# TVR_Rev2_Power.net
KiCad netlist of a schematic drawn in Altium Designer
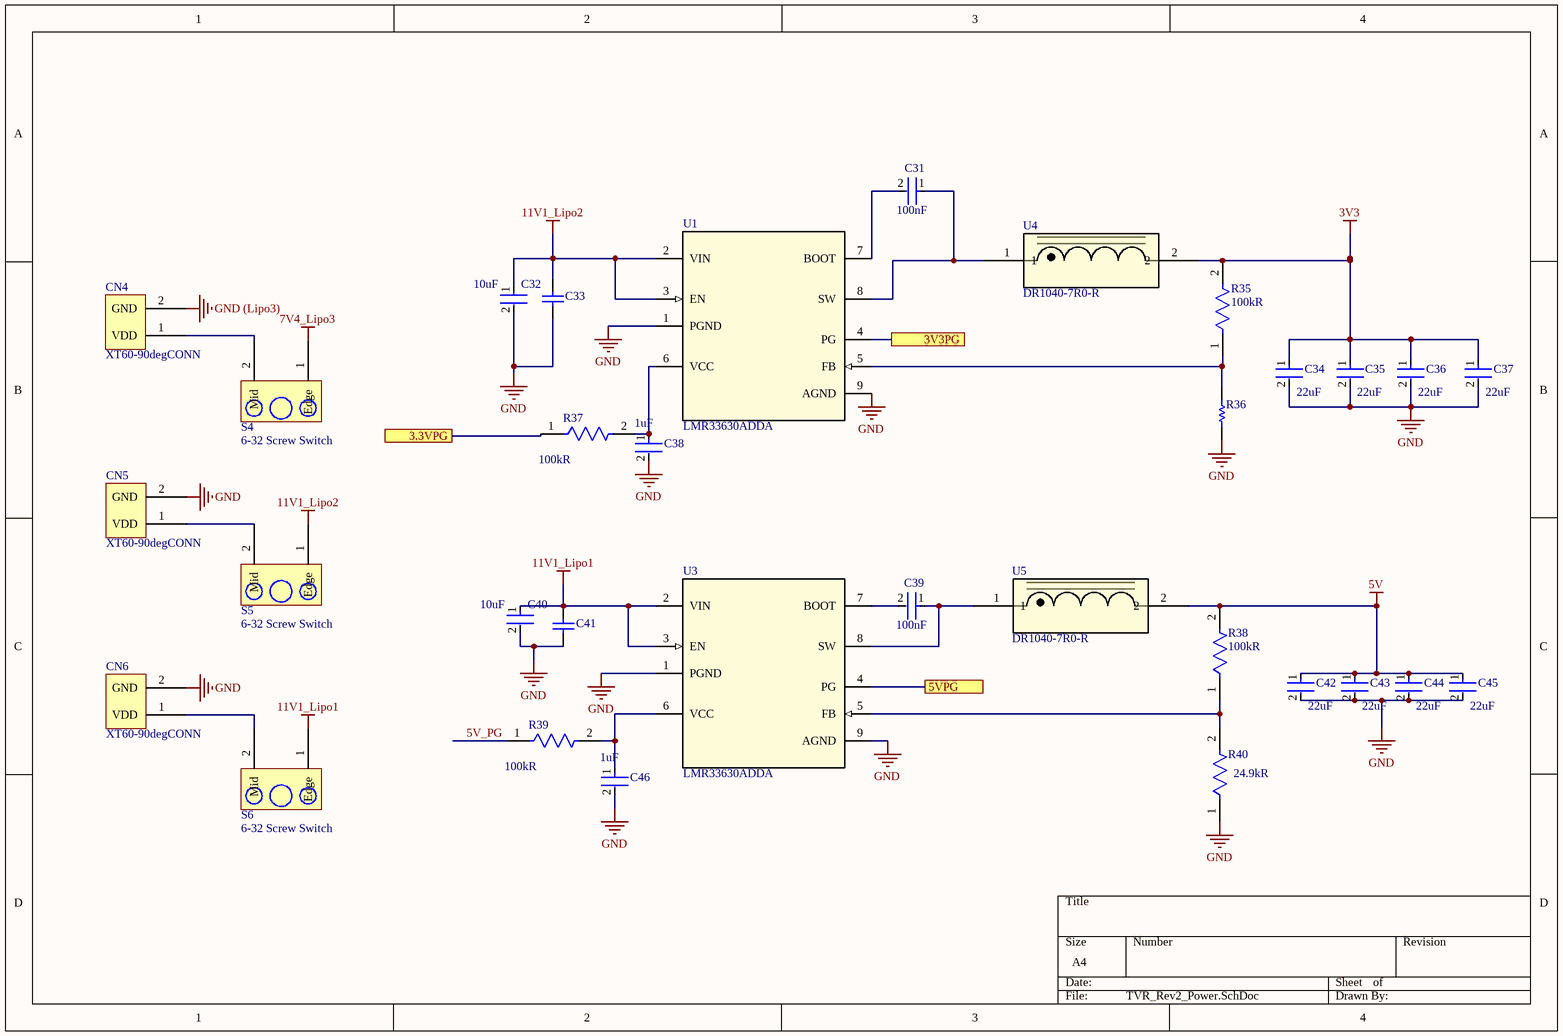
[diagram p0: TVR_Rev2_Power.SchDoc]

(export (version "E")
  (design (tool "Eeschema 10.0.6"))
  (components
    (comp (ref "C31")
      (value "C2012X7T2E104K125AE")
      (footprint "FP-C2012-125-0_45-MFG")
      (description "CAP CER 0.1UF 250V X7T 0805")
      (fields (field (name "CAPACITANCE") "100nF") (field (name "TOLERANCE") "10%"))
      (libsource (lib "Altium Content Vault") (part "b4654b650e69147ec39a6b967a45e02"))
    )
    (comp (ref "C32")
      (value "GRM21BR61E106KA73L")
      (footprint "FP-GRM21B-0_15-IPC_C")
      (description "Chip Multilayer Ceramic Capacitors for General Purpose, 0805, 10uF, X5R, 15%, 10%, 25V")
      (fields
        (field (name "VOLTAGE") "25V")
        (field (name "CAPACITANCE") "10uF")
        (field (name "TOLERANCE") "10%")
      )
      (libsource (lib "Altium Content Vault") (part "b4654b650e69147ec39a6b967a45e02"))
    )
    (comp (ref "C33")
      (value "08051C224KAT2A")
      (footprint "CAPC2013X94X50ML20T25")
      (fields (field (name "MANUFACTURER") "AVX Interconnect / Elco"))
      (libsource (lib "Altium Content Vault") (part "CAP"))
    )
    (comp (ref "C34")
      (value "CL21A226KOQNNNG")
      (footprint "FP-CL21-IPC_A")
      (description "CL21 Series 0805 22uF 16V ±10% Tolerance X5R Multilayer Ceramic Chip Capacitor")
      (fields (field (name "TOLERANCE") "10%") (field (name "CAPACITANCE") "22uF"))
      (libsource (lib "Altium Content Vault") (part "b4654b650e69147ec39a6b967a45e02"))
    )
    (comp (ref "C35")
      (value "CL21A226KOQNNNG")
      (footprint "FP-CL21-IPC_A")
      (description "CL21 Series 0805 22uF 16V ±10% Tolerance X5R Multilayer Ceramic Chip Capacitor")
      (fields (field (name "TOLERANCE") "10%") (field (name "CAPACITANCE") "22uF"))
      (libsource (lib "Altium Content Vault") (part "b4654b650e69147ec39a6b967a45e02"))
    )
    (comp (ref "C36")
      (value "CL21A226KOQNNNG")
      (footprint "FP-CL21-IPC_A")
      (description "CL21 Series 0805 22uF 16V ±10% Tolerance X5R Multilayer Ceramic Chip Capacitor")
      (fields (field (name "TOLERANCE") "10%") (field (name "CAPACITANCE") "22uF"))
      (libsource (lib "Altium Content Vault") (part "b4654b650e69147ec39a6b967a45e02"))
    )
    (comp (ref "C37")
      (value "CL21A226KOQNNNG")
      (footprint "FP-CL21-IPC_A")
      (description "CL21 Series 0805 22uF 16V ±10% Tolerance X5R Multilayer Ceramic Chip Capacitor")
      (fields (field (name "TOLERANCE") "10%") (field (name "CAPACITANCE") "22uF"))
      (libsource (lib "Altium Content Vault") (part "b4654b650e69147ec39a6b967a45e02"))
    )
    (comp (ref "C38")
      (value "C2012X7S2A105K125AE")
      (footprint "FP-C2012-125-IPC_B")
      (description "CAP CER 1UF 100V X7S 0805")
      (fields (field (name "TOLERANCE") "10%") (field (name "CAPACITANCE") "1uF"))
      (libsource (lib "Altium Content Vault") (part "02cd4be3c70576c341d710602a673aa"))
    )
    (comp (ref "C39")
      (value "C2012X7T2E104K125AE")
      (footprint "FP-C2012-125-0_45-MFG")
      (description "CAP CER 0.1UF 250V X7T 0805")
      (fields (field (name "CAPACITANCE") "100nF") (field (name "TOLERANCE") "10%"))
      (libsource (lib "Altium Content Vault") (part "b4654b650e69147ec39a6b967a45e02"))
    )
    (comp (ref "C40")
      (value "GRM21BR61E106KA73L")
      (footprint "FP-GRM21B-0_15-IPC_C")
      (description "Chip Multilayer Ceramic Capacitors for General Purpose, 0805, 10uF, X5R, 15%, 10%, 25V")
      (fields
        (field (name "VOLTAGE") "25V")
        (field (name "CAPACITANCE") "10uF")
        (field (name "TOLERANCE") "10%")
      )
      (libsource (lib "Altium Content Vault") (part "b4654b650e69147ec39a6b967a45e02"))
    )
    (comp (ref "C41")
      (value "08051C224KAT2A")
      (footprint "CAPC2013X94X50ML20T25")
      (fields (field (name "MANUFACTURER") "AVX Interconnect / Elco"))
      (libsource (lib "Altium Content Vault") (part "CAP"))
    )
    (comp (ref "C42")
      (value "CL21A226KOQNNNG")
      (footprint "FP-CL21-IPC_A")
      (description "CL21 Series 0805 22uF 16V ±10% Tolerance X5R Multilayer Ceramic Chip Capacitor")
      (fields (field (name "TOLERANCE") "10%") (field (name "CAPACITANCE") "22uF"))
      (libsource (lib "Altium Content Vault") (part "b4654b650e69147ec39a6b967a45e02"))
    )
    (comp (ref "C43")
      (value "CL21A226KOQNNNG")
      (footprint "FP-CL21-IPC_A")
      (description "CL21 Series 0805 22uF 16V ±10% Tolerance X5R Multilayer Ceramic Chip Capacitor")
      (fields (field (name "TOLERANCE") "10%") (field (name "CAPACITANCE") "22uF"))
      (libsource (lib "Altium Content Vault") (part "b4654b650e69147ec39a6b967a45e02"))
    )
    (comp (ref "C44")
      (value "CL21A226KOQNNNG")
      (footprint "FP-CL21-IPC_A")
      (description "CL21 Series 0805 22uF 16V ±10% Tolerance X5R Multilayer Ceramic Chip Capacitor")
      (fields (field (name "TOLERANCE") "10%") (field (name "CAPACITANCE") "22uF"))
      (libsource (lib "Altium Content Vault") (part "b4654b650e69147ec39a6b967a45e02"))
    )
    (comp (ref "C45")
      (value "CL21A226KOQNNNG")
      (footprint "FP-CL21-IPC_A")
      (description "CL21 Series 0805 22uF 16V ±10% Tolerance X5R Multilayer Ceramic Chip Capacitor")
      (fields (field (name "TOLERANCE") "10%") (field (name "CAPACITANCE") "22uF"))
      (libsource (lib "Altium Content Vault") (part "b4654b650e69147ec39a6b967a45e02"))
    )
    (comp (ref "C46")
      (value "C2012X7S2A105K125AE")
      (footprint "FP-C2012-125-IPC_B")
      (description "CAP CER 1UF 100V X7S 0805")
      (fields (field (name "TOLERANCE") "10%") (field (name "CAPACITANCE") "1uF"))
      (libsource (lib "Altium Content Vault") (part "02cd4be3c70576c341d710602a673aa"))
    )
    (comp (ref "CN4")
      (value "XT60-90degCONN")
      (footprint "XT60-90CONN")
      (libsource (lib "Schlib2") (part "XT60-90degCONN"))
    )
    (comp (ref "CN5")
      (value "XT60-90degCONN")
      (footprint "XT60-90CONN")
      (libsource (lib "Schlib2") (part "XT60-90degCONN"))
    )
    (comp (ref "CN6")
      (value "XT60-90degCONN")
      (footprint "XT60-90CONN")
      (libsource (lib "Schlib2") (part "XT60-90degCONN"))
    )
    (comp (ref "R35")
      (value "RC0805FR-07100KL")
      (footprint "FP-RC0805-0_6-IPC_C")
      (description "RES 100K OHM 1% 1/8W 0805")
      (fields (field (name "TOLERANCE") "1%") (field (name "RESISTANCE") "100kR"))
      (libsource (lib "Altium Content Vault") (part "1029c3af85768c4190bb7ad29bc67b5"))
    )
    (comp (ref "R36")
      (value "RC0805FR-0743K2L")
      (footprint "RESC2013X60X35NL10T20")
      (fields (field (name "MANUFACTURER") "Yageo"))
      (libsource (lib "Altium Content Vault") (part "RES"))
    )
    (comp (ref "R37")
      (value "RC0805FR-07100KL")
      (footprint "FP-RC0805-0_6-IPC_C")
      (description "RES 100K OHM 1% 1/8W 0805")
      (fields (field (name "TOLERANCE") "1%") (field (name "RESISTANCE") "100kR"))
      (libsource (lib "Altium Content Vault") (part "1029c3af85768c4190bb7ad29bc67b5"))
    )
    (comp (ref "R38")
      (value "RC0805FR-07100KL")
      (footprint "FP-RC0805-0_6-IPC_C")
      (description "RES 100K OHM 1% 1/8W 0805")
      (fields (field (name "TOLERANCE") "1%") (field (name "RESISTANCE") "100kR"))
      (libsource (lib "Altium Content Vault") (part "1029c3af85768c4190bb7ad29bc67b5"))
    )
    (comp (ref "R39")
      (value "RC0805FR-07100KL")
      (footprint "FP-RC0805-0_6-IPC_C")
      (description "RES 100K OHM 1% 1/8W 0805")
      (fields (field (name "TOLERANCE") "1%") (field (name "RESISTANCE") "100kR"))
      (libsource (lib "Altium Content Vault") (part "1029c3af85768c4190bb7ad29bc67b5"))
    )
    (comp (ref "R40")
      (value "RMCF1210FT24K9")
      (footprint "FP-RMCF1210-MFG")
      (description "24.9kΩ ±1% 0.5W 1210 Thick Film Chip Resistor AEC-Q200 compliant")
      (fields (field (name "RESISTANCE") "24.9kR") (field (name "TOLERANCE") "1%"))
      (libsource (lib "Altium Content Vault") (part "1029c3af85768c4190bb7ad29bc67b5"))
    )
    (comp (ref "S4")
      (value "6-32 Screw Switch")
      (footprint "6-32 Screw Switch")
      (libsource (lib "Schlib2") (part "6-32 Screw Switch"))
    )
    (comp (ref "S5")
      (value "6-32 Screw Switch")
      (footprint "6-32 Screw Switch")
      (libsource (lib "Schlib2") (part "6-32 Screw Switch"))
    )
    (comp (ref "S6")
      (value "6-32 Screw Switch")
      (footprint "6-32 Screw Switch")
      (libsource (lib "Schlib2") (part "6-32 Screw Switch"))
    )
    (comp (ref "U1")
      (value "LMR33630ADDA")
      (footprint "DDA0008J")
      (description "No Description Available")
      (libsource (lib "TVR") (part "LMR33630ADDA"))
    )
    (comp (ref "U3")
      (value "LMR33630ADDA")
      (footprint "DDA0008J")
      (description "No Description Available")
      (libsource (lib "TVR") (part "LMR33630ADDA"))
    )
    (comp (ref "U4")
      (value "DR1040-7R0-R")
      (footprint "DR1040-7R0-R_EAT")
      (description "No Description Available")
      (libsource (lib "TVR") (part "DR1040-7R0-R"))
    )
    (comp (ref "U5")
      (value "DR1040-7R0-R")
      (footprint "DR1040-7R0-R_EAT")
      (description "No Description Available")
      (libsource (lib "TVR") (part "DR1040-7R0-R"))
    )
  )
  (nets
    (net (code "1") (name "/3.3VPG") (class "Default")
      (node (ref "R37") (pin "1") (pinfunction "1_1") (pintype "passive"))
    )
    (net (code "2") (name "/3V3PG") (class "Default")
      (node (ref "U1") (pin "4") (pinfunction "PG_4") (pintype "open_collector"))
    )
    (net (code "3") (name "/5VPG") (class "Default")
      (node (ref "U3") (pin "4") (pinfunction "PG_4") (pintype "open_collector"))
    )
    (net (code "4") (name "/5V_PG") (class "Default")
      (node (ref "R39") (pin "1") (pinfunction "1_1") (pintype "passive"))
    )
    (net (code "5") (name "3V3") (class "Default")
      (node (ref "C34") (pin "1") (pinfunction "1_1") (pintype "passive"))
      (node (ref "C35") (pin "1") (pinfunction "1_1") (pintype "passive"))
      (node (ref "C36") (pin "1") (pinfunction "1_1") (pintype "passive"))
      (node (ref "C37") (pin "1") (pinfunction "1_1") (pintype "passive"))
      (node (ref "R35") (pin "2") (pinfunction "2_2") (pintype "passive"))
      (node (ref "U4") (pin "2") (pinfunction "2_2") (pintype "passive"))
    )
    (net (code "6") (name "5V") (class "Default")
      (node (ref "C42") (pin "1") (pinfunction "1_1") (pintype "passive"))
      (node (ref "C43") (pin "1") (pinfunction "1_1") (pintype "passive"))
      (node (ref "C44") (pin "1") (pinfunction "1_1") (pintype "passive"))
      (node (ref "C45") (pin "1") (pinfunction "1_1") (pintype "passive"))
      (node (ref "R38") (pin "2") (pinfunction "2_2") (pintype "passive"))
      (node (ref "U5") (pin "2") (pinfunction "2_2") (pintype "passive"))
    )
    (net (code "7") (name "7V4_Lipo3") (class "Default")
      (node (ref "S4") (pin "1") (pinfunction "Edge_1") (pintype "passive"))
    )
    (net (code "8") (name "11V1_Lipo1") (class "Default")
      (node (ref "C40") (pin "1") (pinfunction "1_1") (pintype "passive"))
      (node (ref "C41") (pin "2") (pinfunction "2_2") (pintype "passive"))
      (node (ref "S6") (pin "1") (pinfunction "Edge_1") (pintype "passive"))
      (node (ref "U3") (pin "2") (pinfunction "VIN_2") (pintype "power_in"))
      (node (ref "U3") (pin "3") (pinfunction "EN_3") (pintype "input"))
    )
    (net (code "9") (name "11V1_Lipo2") (class "Default")
      (node (ref "C32") (pin "1") (pinfunction "1_1") (pintype "passive"))
      (node (ref "C33") (pin "2") (pinfunction "2_2") (pintype "passive"))
      (node (ref "S5") (pin "1") (pinfunction "Edge_1") (pintype "passive"))
      (node (ref "U1") (pin "2") (pinfunction "VIN_2") (pintype "power_in"))
      (node (ref "U1") (pin "3") (pinfunction "EN_3") (pintype "input"))
    )
    (net (code "10") (name "GND") (class "Default")
      (node (ref "C32") (pin "2") (pinfunction "2_2") (pintype "passive"))
      (node (ref "C33") (pin "1") (pinfunction "1_1") (pintype "passive"))
      (node (ref "C34") (pin "2") (pinfunction "2_2") (pintype "passive"))
      (node (ref "C35") (pin "2") (pinfunction "2_2") (pintype "passive"))
      (node (ref "C36") (pin "2") (pinfunction "2_2") (pintype "passive"))
      (node (ref "C37") (pin "2") (pinfunction "2_2") (pintype "passive"))
      (node (ref "C38") (pin "2") (pinfunction "2_2") (pintype "passive"))
      (node (ref "C40") (pin "2") (pinfunction "2_2") (pintype "passive"))
      (node (ref "C41") (pin "1") (pinfunction "1_1") (pintype "passive"))
      (node (ref "C42") (pin "2") (pinfunction "2_2") (pintype "passive"))
      (node (ref "C43") (pin "2") (pinfunction "2_2") (pintype "passive"))
      (node (ref "C44") (pin "2") (pinfunction "2_2") (pintype "passive"))
      (node (ref "C45") (pin "2") (pinfunction "2_2") (pintype "passive"))
      (node (ref "C46") (pin "2") (pinfunction "2_2") (pintype "passive"))
      (node (ref "CN5") (pin "2") (pinfunction "GND_2") (pintype "passive"))
      (node (ref "CN6") (pin "2") (pinfunction "GND_2") (pintype "passive"))
      (node (ref "R36") (pin "1") (pinfunction "1_1") (pintype "passive"))
      (node (ref "R40") (pin "1") (pinfunction "1_1") (pintype "passive"))
      (node (ref "U1") (pin "1") (pinfunction "PGND_1") (pintype "power_in"))
      (node (ref "U1") (pin "9") (pinfunction "AGND_9") (pintype "passive"))
      (node (ref "U3") (pin "1") (pinfunction "PGND_1") (pintype "power_in"))
      (node (ref "U3") (pin "9") (pinfunction "AGND_9") (pintype "passive"))
    )
    (net (code "11") (name "GND (Lipo3)") (class "Default")
      (node (ref "CN4") (pin "2") (pinfunction "GND_2") (pintype "passive"))
    )
    (net (code "12") (name "Net-(CN4-VDD)") (class "Default")
      (node (ref "CN4") (pin "1") (pinfunction "VDD_1") (pintype "passive"))
      (node (ref "S4") (pin "2") (pinfunction "Mid_2") (pintype "passive"))
    )
    (net (code "13") (name "Net-(CN5-VDD)") (class "Default")
      (node (ref "CN5") (pin "1") (pinfunction "VDD_1") (pintype "passive"))
      (node (ref "S5") (pin "2") (pinfunction "Mid_2") (pintype "passive"))
    )
    (net (code "14") (name "Net-(CN6-VDD)") (class "Default")
      (node (ref "CN6") (pin "1") (pinfunction "VDD_1") (pintype "passive"))
      (node (ref "S6") (pin "2") (pinfunction "Mid_2") (pintype "passive"))
    )
    (net (code "15") (name "Net-(U1-BOOT)") (class "Default")
      (node (ref "C31") (pin "2") (pinfunction "2_2") (pintype "passive"))
      (node (ref "U1") (pin "7") (pinfunction "BOOT_7") (pintype "power_in"))
    )
    (net (code "16") (name "Net-(U1-FB)") (class "Default")
      (node (ref "R35") (pin "1") (pinfunction "1_1") (pintype "passive"))
      (node (ref "R36") (pin "2") (pinfunction "2_2") (pintype "passive"))
      (node (ref "U1") (pin "5") (pinfunction "FB_5") (pintype "input"))
    )
    (net (code "17") (name "Net-(U1-SW)") (class "Default")
      (node (ref "C31") (pin "1") (pinfunction "1_1") (pintype "passive"))
      (node (ref "U1") (pin "8") (pinfunction "SW_8") (pintype "power_in"))
      (node (ref "U4") (pin "1") (pinfunction "1_1") (pintype "passive"))
    )
    (net (code "18") (name "Net-(U1-VCC)") (class "Default")
      (node (ref "C38") (pin "1") (pinfunction "1_1") (pintype "passive"))
      (node (ref "R37") (pin "2") (pinfunction "2_2") (pintype "passive"))
      (node (ref "U1") (pin "6") (pinfunction "VCC_6") (pintype "power_in"))
    )
    (net (code "19") (name "Net-(U3-BOOT)") (class "Default")
      (node (ref "C39") (pin "2") (pinfunction "2_2") (pintype "passive"))
      (node (ref "U3") (pin "7") (pinfunction "BOOT_7") (pintype "power_in"))
    )
    (net (code "20") (name "Net-(U3-FB)") (class "Default")
      (node (ref "R38") (pin "1") (pinfunction "1_1") (pintype "passive"))
      (node (ref "R40") (pin "2") (pinfunction "2_2") (pintype "passive"))
      (node (ref "U3") (pin "5") (pinfunction "FB_5") (pintype "input"))
    )
    (net (code "21") (name "Net-(U3-SW)") (class "Default")
      (node (ref "C39") (pin "1") (pinfunction "1_1") (pintype "passive"))
      (node (ref "U3") (pin "8") (pinfunction "SW_8") (pintype "power_in"))
      (node (ref "U5") (pin "1") (pinfunction "1_1") (pintype "passive"))
    )
    (net (code "22") (name "Net-(U3-VCC)") (class "Default")
      (node (ref "C46") (pin "1") (pinfunction "1_1") (pintype "passive"))
      (node (ref "R39") (pin "2") (pinfunction "2_2") (pintype "passive"))
      (node (ref "U3") (pin "6") (pinfunction "VCC_6") (pintype "power_in"))
    )
  )
)
